# PGS_4.net
KiCad netlist of a schematic drawn in Altium Designer
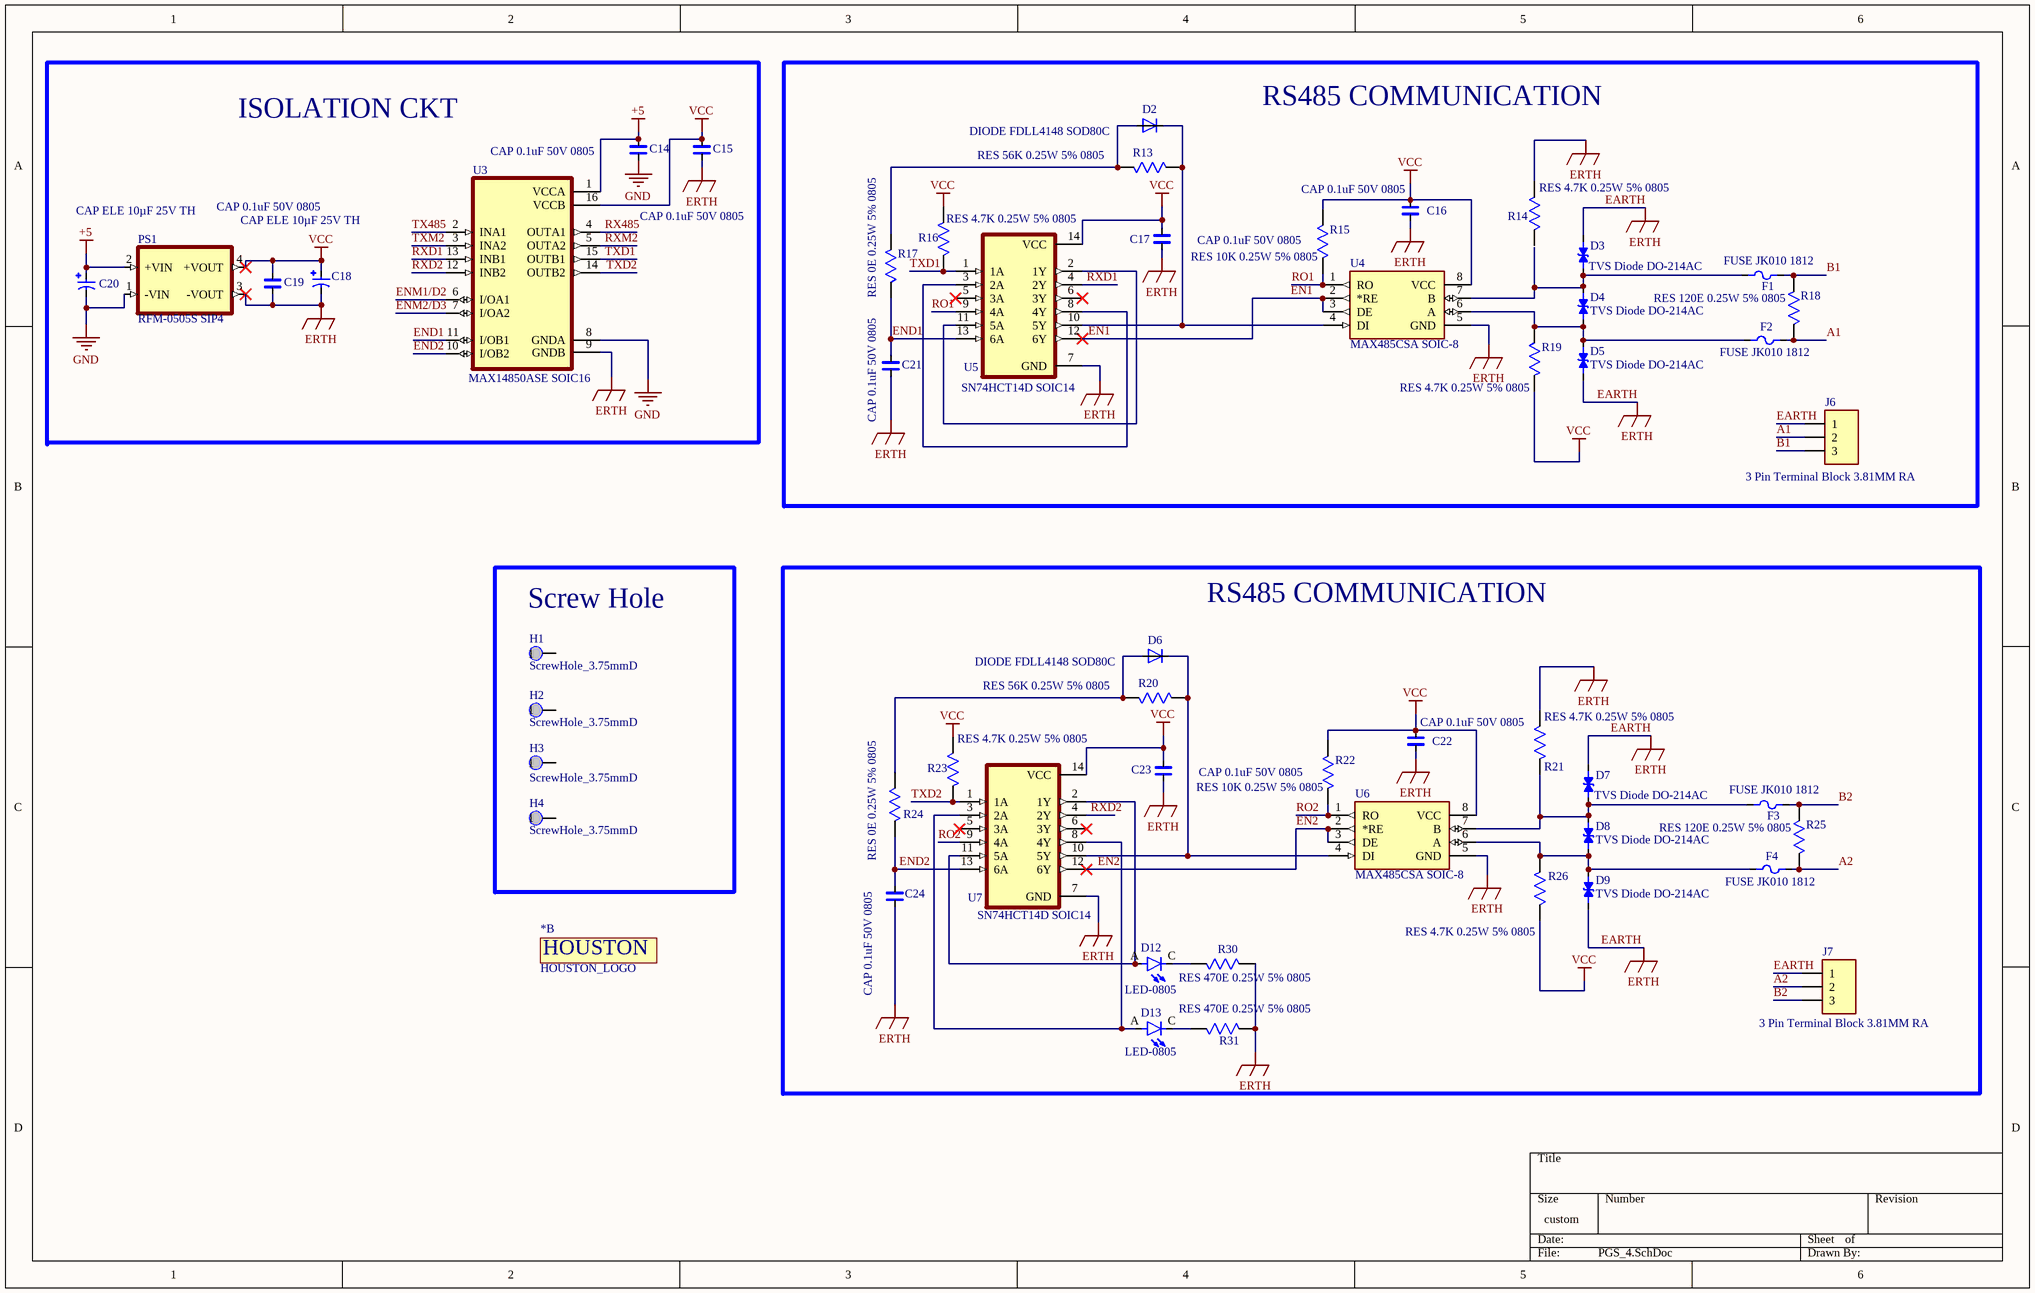
[diagram p0: PGS_4.SchDoc]

(export (version "E")
  (design (tool "Eeschema 10.0.6"))
  (components
    (comp (ref "*")
      (value "HOUSTON_LOGO")
      (footprint "HOUSTON_LOGO")
      (libsource (lib "PGS") (part "HOUSTON_LOGO"))
    )
    (comp (ref "C14")
      (value "CAP 0.1uF 50V 0805")
      (footprint "CAP CER 0.1uF/50V 5%")
      (description "CAP CER 0.1uF/50V  Ceramic Capacitor X7R 0805 (2012 Metric)")
      (fields (field (name "MF") "Samsung") (field (name "MP") "CL21B104KCFNNNE"))
      (libsource (lib "PGS") (part "CAP CER 0.1uF/50V 5%"))
    )
    (comp (ref "C15")
      (value "CAP 0.1uF 50V 0805")
      (footprint "CAP CER 0.1uF/50V 5%")
      (description "CAP CER 0.1uF/50V  Ceramic Capacitor X7R 0805 (2012 Metric)")
      (fields (field (name "MF") "Samsung") (field (name "MP") "CL21B104KCFNNNE"))
      (libsource (lib "PGS") (part "CAP CER 0.1uF/50V 5%"))
    )
    (comp (ref "C16")
      (value "CAP 0.1uF 50V 0805")
      (footprint "CAP CER 0.1uF/50V 5%")
      (description "CAP CER 0.1uF/50V  Ceramic Capacitor X7R 0805 (2012 Metric)")
      (fields (field (name "MF") "Samsung") (field (name "MP") "CL21B104KCFNNNE"))
      (libsource (lib "PGS") (part "CAP CER 0.1uF/50V 5%"))
    )
    (comp (ref "C17")
      (value "CAP 0.1uF 50V 0805")
      (footprint "CAP CER 0.1uF/50V 5%")
      (description "CAP CER 0.1uF/50V  Ceramic Capacitor X7R 0805 (2012 Metric)")
      (fields (field (name "MF") "Samsung") (field (name "MP") "CL21B104KCFNNNE"))
      (libsource (lib "PGS") (part "CAP CER 0.1uF/50V 5%"))
    )
    (comp (ref "C18")
      (value "CAP ELE 10µF 25V TH")
      (footprint "CAP ELE 10µF 25V TH")
      (description "10µF 25V Aluminum Electrolytic Capacitors Radial Lead Type TH, Dia-5mm, Pitch-2mm ECEA1EN100UI")
      (fields (field (name "MF") "Panasonic") (field (name "DIGI-KEY_PART_NUMBER") "ECE-A1EN100UI-ND"))
      (libsource (lib "PGS") (part "CAP ELE 10µF 25V TH"))
    )
    (comp (ref "C19")
      (value "CAP 0.1uF 50V 0805")
      (footprint "CAP CER 0.1uF/50V 5%")
      (description "CAP CER 0.1uF/50V  Ceramic Capacitor X7R 0805 (2012 Metric)")
      (fields (field (name "MF") "Samsung") (field (name "MP") "CL21B104KCFNNNE"))
      (libsource (lib "PGS") (part "CAP CER 0.1uF/50V 5%"))
    )
    (comp (ref "C20")
      (value "CAP ELE 10µF 25V TH")
      (footprint "CAP ELE 10µF 25V TH")
      (description "10µF 25V Aluminum Electrolytic Capacitors Radial Lead Type TH, Dia-5mm, Pitch-2mm ECEA1EN100UI")
      (fields (field (name "MF") "Panasonic") (field (name "DIGI-KEY_PART_NUMBER") "ECE-A1EN100UI-ND"))
      (libsource (lib "PGS") (part "CAP ELE 10µF 25V TH"))
    )
    (comp (ref "C21")
      (value "CAP 0.1uF 50V 0805")
      (footprint "CAP CER 0.1uF/50V 5%")
      (description "CAP CER 0.1uF/50V  Ceramic Capacitor X7R 0805 (2012 Metric)")
      (fields (field (name "MF") "Samsung") (field (name "MP") "CL21B104KCFNNNE"))
      (libsource (lib "PGS") (part "CAP CER 0.1uF/50V 5%"))
    )
    (comp (ref "C22")
      (value "CAP 0.1uF 50V 0805")
      (footprint "CAP CER 0.1uF/50V 5%")
      (description "CAP CER 0.1uF/50V  Ceramic Capacitor X7R 0805 (2012 Metric)")
      (fields (field (name "MF") "Samsung") (field (name "MP") "CL21B104KCFNNNE"))
      (libsource (lib "PGS") (part "CAP CER 0.1uF/50V 5%"))
    )
    (comp (ref "C23")
      (value "CAP 0.1uF 50V 0805")
      (footprint "CAP CER 0.1uF/50V 5%")
      (description "CAP CER 0.1uF/50V  Ceramic Capacitor X7R 0805 (2012 Metric)")
      (fields (field (name "MF") "Samsung") (field (name "MP") "CL21B104KCFNNNE"))
      (libsource (lib "PGS") (part "CAP CER 0.1uF/50V 5%"))
    )
    (comp (ref "C24")
      (value "CAP 0.1uF 50V 0805")
      (footprint "CAP CER 0.1uF/50V 5%")
      (description "CAP CER 0.1uF/50V  Ceramic Capacitor X7R 0805 (2012 Metric)")
      (fields (field (name "MF") "Samsung") (field (name "MP") "CL21B104KCFNNNE"))
      (libsource (lib "PGS") (part "CAP CER 0.1uF/50V 5%"))
    )
    (comp (ref "D2")
      (value "DIODE FDLL4148 SOD80C")
      (footprint "DIODE SOD80C")
      (description "FDLL4148 Diode Standard 75V 200mA _DC_ Surface Mount LLDS; MiniMelf DIODE SOD80C PMLL4148L")
      (fields (field (name "MF") "Nexperia USA") (field (name "MP") "PMLL4148L"))
      (libsource (lib "PGS") (part "DIODE FDLL4148 SOD80C"))
    )
    (comp (ref "D3")
      (value "TVS Diode DO-214AC")
      (footprint "TVS Diode DO-214AC")
      (description "TVS Diode BiDirectional LittileFuse 1.5SMC6.8CA DO-214AC 6V8C")
      (fields (field (name "MP") "SMAJ7.5CA"))
      (libsource (lib "PGS") (part "TVS Diode DO-214AC"))
    )
    (comp (ref "D4")
      (value "TVS Diode DO-214AC")
      (footprint "TVS Diode DO-214AC")
      (description "TVS Diode BiDirectional LittileFuse 1.5SMC6.8CA DO-214AC 6V8C")
      (fields (field (name "MP") "SMAJ7.5CA"))
      (libsource (lib "PGS") (part "TVS Diode DO-214AC"))
    )
    (comp (ref "D5")
      (value "TVS Diode DO-214AC")
      (footprint "TVS Diode DO-214AC")
      (description "TVS Diode BiDirectional LittileFuse 1.5SMC6.8CA DO-214AC 6V8C")
      (fields (field (name "MP") "SMAJ7.5CA"))
      (libsource (lib "PGS") (part "TVS Diode DO-214AC"))
    )
    (comp (ref "D6")
      (value "DIODE FDLL4148 SOD80C")
      (footprint "DIODE SOD80C")
      (description "FDLL4148 Diode Standard 75V 200mA _DC_ Surface Mount LLDS; MiniMelf DIODE SOD80C PMLL4148L")
      (fields (field (name "MF") "Nexperia USA") (field (name "MP") "PMLL4148L"))
      (libsource (lib "PGS") (part "DIODE FDLL4148 SOD80C"))
    )
    (comp (ref "D7")
      (value "TVS Diode DO-214AC")
      (footprint "TVS Diode DO-214AC")
      (description "TVS Diode BiDirectional LittileFuse 1.5SMC6.8CA DO-214AC 6V8C")
      (fields (field (name "MP") "SMAJ7.5CA"))
      (libsource (lib "PGS") (part "TVS Diode DO-214AC"))
    )
    (comp (ref "D8")
      (value "TVS Diode DO-214AC")
      (footprint "TVS Diode DO-214AC")
      (description "TVS Diode BiDirectional LittileFuse 1.5SMC6.8CA DO-214AC 6V8C")
      (fields (field (name "MP") "SMAJ7.5CA"))
      (libsource (lib "PGS") (part "TVS Diode DO-214AC"))
    )
    (comp (ref "D9")
      (value "TVS Diode DO-214AC")
      (footprint "TVS Diode DO-214AC")
      (description "TVS Diode BiDirectional LittileFuse 1.5SMC6.8CA DO-214AC 6V8C")
      (fields (field (name "MP") "SMAJ7.5CA"))
      (libsource (lib "PGS") (part "TVS Diode DO-214AC"))
    )
    (comp (ref "D12")
      (value "LED-0805")
      (footprint "LED-0805")
      (description "Red 640nm LED Indication - Discrete 1.85V 0805 (2012 Metric) SMT APT2012SRCPRV")
      (fields (field (name "MF") "Kingbright") (field (name "MP") "APT2012SRCPRV"))
      (libsource (lib "PGS") (part "LED-0805"))
    )
    (comp (ref "D13")
      (value "LED-0805")
      (footprint "LED-0805")
      (description "Red 640nm LED Indication - Discrete 1.85V 0805 (2012 Metric) SMT APT2012SRCPRV")
      (fields (field (name "MF") "Kingbright") (field (name "MP") "APT2012SRCPRV"))
      (libsource (lib "PGS") (part "LED-0805"))
    )
    (comp (ref "F1")
      (value "FUSE JK010 1812")
      (footprint "FUSE JK010 1812")
      (fields (field (name "MP") "MF-MSMF010-2") (field (name "MF") "Bourns"))
      (libsource (lib "PGS") (part "FUSE JK010 1812"))
    )
    (comp (ref "F2")
      (value "FUSE JK010 1812")
      (footprint "FUSE JK010 1812")
      (fields (field (name "MP") "MF-MSMF010-2") (field (name "MF") "Bourns"))
      (libsource (lib "PGS") (part "FUSE JK010 1812"))
    )
    (comp (ref "F3")
      (value "FUSE JK010 1812")
      (footprint "FUSE JK010 1812")
      (fields (field (name "MP") "MF-MSMF010-2") (field (name "MF") "Bourns"))
      (libsource (lib "PGS") (part "FUSE JK010 1812"))
    )
    (comp (ref "F4")
      (value "FUSE JK010 1812")
      (footprint "FUSE JK010 1812")
      (fields (field (name "MP") "MF-MSMF010-2") (field (name "MF") "Bourns"))
      (libsource (lib "PGS") (part "FUSE JK010 1812"))
    )
    (comp (ref "H1")
      (value "ScrewHole_3.75mmD")
      (footprint "ScrewHole_3.75mmD - duplicate")
      (description "SCREW HEAD DIA 4.5MM, SREW LEG DIA 3 MM")
      (libsource (lib "PGS") (part "ScrewHole_3.75mmD"))
    )
    (comp (ref "H2")
      (value "ScrewHole_3.75mmD")
      (footprint "ScrewHole_3.75mmD - duplicate")
      (description "SCREW HEAD DIA 4.5MM, SREW LEG DIA 3 MM")
      (libsource (lib "PGS") (part "ScrewHole_3.75mmD"))
    )
    (comp (ref "H3")
      (value "ScrewHole_3.75mmD")
      (footprint "ScrewHole_3.75mmD - duplicate")
      (description "SCREW HEAD DIA 4.5MM, SREW LEG DIA 3 MM")
      (libsource (lib "PGS") (part "ScrewHole_3.75mmD"))
    )
    (comp (ref "H4")
      (value "ScrewHole_3.75mmD")
      (footprint "ScrewHole_3.75mmD - duplicate")
      (description "SCREW HEAD DIA 4.5MM, SREW LEG DIA 3 MM")
      (libsource (lib "PGS") (part "ScrewHole_3.75mmD"))
    )
    (comp (ref "J6")
      (value "3 Pin Terminal Block 3.81MM RA")
      (footprint "3 Pin Terminal Block 3.81MM RA")
      (description "3 Pin Terminal Block HDR 3.81MM THT RA 284513-3")
      (fields (field (name "MP") "284513-3") (field (name "MF") "TE Connectivity"))
      (libsource (lib "PGS") (part "3 Pin Terminal Block 3.81MM RA"))
    )
    (comp (ref "J7")
      (value "3 Pin Terminal Block 3.81MM RA")
      (footprint "3 Pin Terminal Block 3.81MM RA")
      (description "3 Pin Terminal Block HDR 3.81MM THT RA 284513-3")
      (fields (field (name "MP") "284513-3") (field (name "MF") "TE Connectivity"))
      (libsource (lib "PGS") (part "3 Pin Terminal Block 3.81MM RA"))
    )
    (comp (ref "PS1")
      (value "RFM-0505S SIP4")
      (footprint "RFM-0505S")
      (fields (field (name "MF") "Recom Power") (field (name "MP") "RFM-0505S"))
      (libsource (lib "PGS") (part "RFM-0505S"))
    )
    (comp (ref "R13")
      (value "RES 56K 0.25W 5% 0805")
      (footprint "RES 0805 10K/0.25W 5%")
      (description "RESISTOR, THICK FILM, 10K, 5%, 0805 0.25W")
      (fields (field (name "MP") "ERJ-6GEYJ103V") (field (name "MF") "Panasonic Electronic"))
      (libsource (lib "PGS") (part "RES 10K 0.25W 5% 0805"))
    )
    (comp (ref "R14")
      (value "RES 4.7K 0.25W 5% 0805")
      (footprint "RES 0805 10K/0.25W 5%")
      (description "RESISTOR, THICK FILM, 10K, 5%, 0805 0.25W")
      (fields (field (name "MP") "ERJ-6GEYJ103V") (field (name "MF") "Panasonic Electronic"))
      (libsource (lib "PGS") (part "RES 10K 0.25W 5% 0805"))
    )
    (comp (ref "R15")
      (value "RES 10K 0.25W 5% 0805")
      (footprint "RES 0805 10K/0.25W 5%")
      (description "RESISTOR, THICK FILM, 10K, 5%, 0805 0.25W")
      (fields (field (name "MP") "ERJ-6GEYJ103V") (field (name "MF") "Panasonic Electronic"))
      (libsource (lib "PGS") (part "RES 10K 0.25W 5% 0805"))
    )
    (comp (ref "R16")
      (value "RES 4.7K 0.25W 5% 0805")
      (footprint "RES 0805 10K/0.25W 5%")
      (description "RESISTOR, THICK FILM, 10K, 5%, 0805 0.25W")
      (fields (field (name "MP") "ERJ-6GEYJ103V") (field (name "MF") "Panasonic Electronic"))
      (libsource (lib "PGS") (part "RES 10K 0.25W 5% 0805"))
    )
    (comp (ref "R17")
      (value "RES 0E 0.25W 5% 0805")
      (footprint "RES 0805 10K/0.25W 5%")
      (description "RESISTOR, THICK FILM, 10K, 5%, 0805 0.25W")
      (fields (field (name "MP") "ERJ-6GEYJ103V") (field (name "MF") "Panasonic Electronic"))
      (libsource (lib "PGS") (part "RES 10K 0.25W 5% 0805"))
    )
    (comp (ref "R18")
      (value "RES 120E 0.25W 5% 0805")
      (footprint "RES 0805 10K/0.25W 5%")
      (description "RESISTOR, THICK FILM, 10K, 5%, 0805 0.25W")
      (fields (field (name "MP") "ERJ-6GEYJ103V") (field (name "MF") "Panasonic Electronic"))
      (libsource (lib "PGS") (part "RES 10K 0.25W 5% 0805"))
    )
    (comp (ref "R19")
      (value "RES 4.7K 0.25W 5% 0805")
      (footprint "RES 0805 10K/0.25W 5%")
      (description "RESISTOR, THICK FILM, 10K, 5%, 0805 0.25W")
      (fields (field (name "MP") "ERJ-6GEYJ103V") (field (name "MF") "Panasonic Electronic"))
      (libsource (lib "PGS") (part "RES 10K 0.25W 5% 0805"))
    )
    (comp (ref "R20")
      (value "RES 56K 0.25W 5% 0805")
      (footprint "RES 0805 10K/0.25W 5%")
      (description "RESISTOR, THICK FILM, 10K, 5%, 0805 0.25W")
      (fields (field (name "MP") "ERJ-6GEYJ103V") (field (name "MF") "Panasonic Electronic"))
      (libsource (lib "PGS") (part "RES 10K 0.25W 5% 0805"))
    )
    (comp (ref "R21")
      (value "RES 4.7K 0.25W 5% 0805")
      (footprint "RES 0805 10K/0.25W 5%")
      (description "RESISTOR, THICK FILM, 10K, 5%, 0805 0.25W")
      (fields (field (name "MP") "ERJ-6GEYJ103V") (field (name "MF") "Panasonic Electronic"))
      (libsource (lib "PGS") (part "RES 10K 0.25W 5% 0805"))
    )
    (comp (ref "R22")
      (value "RES 10K 0.25W 5% 0805")
      (footprint "RES 0805 10K/0.25W 5%")
      (description "RESISTOR, THICK FILM, 10K, 5%, 0805 0.25W")
      (fields (field (name "MP") "ERJ-6GEYJ103V") (field (name "MF") "Panasonic Electronic"))
      (libsource (lib "PGS") (part "RES 10K 0.25W 5% 0805"))
    )
    (comp (ref "R23")
      (value "RES 4.7K 0.25W 5% 0805")
      (footprint "RES 0805 10K/0.25W 5%")
      (description "RESISTOR, THICK FILM, 10K, 5%, 0805 0.25W")
      (fields (field (name "MP") "ERJ-6GEYJ103V") (field (name "MF") "Panasonic Electronic"))
      (libsource (lib "PGS") (part "RES 10K 0.25W 5% 0805"))
    )
    (comp (ref "R24")
      (value "RES 0E 0.25W 5% 0805")
      (footprint "RES 0805 10K/0.25W 5%")
      (description "RESISTOR, THICK FILM, 10K, 5%, 0805 0.25W")
      (fields (field (name "MP") "ERJ-6GEYJ103V") (field (name "MF") "Panasonic Electronic"))
      (libsource (lib "PGS") (part "RES 10K 0.25W 5% 0805"))
    )
    (comp (ref "R25")
      (value "RES 120E 0.25W 5% 0805")
      (footprint "RES 0805 10K/0.25W 5%")
      (description "RESISTOR, THICK FILM, 10K, 5%, 0805 0.25W")
      (fields (field (name "MP") "ERJ-6GEYJ103V") (field (name "MF") "Panasonic Electronic"))
      (libsource (lib "PGS") (part "RES 10K 0.25W 5% 0805"))
    )
    (comp (ref "R26")
      (value "RES 4.7K 0.25W 5% 0805")
      (footprint "RES 0805 10K/0.25W 5%")
      (description "RESISTOR, THICK FILM, 10K, 5%, 0805 0.25W")
      (fields (field (name "MP") "ERJ-6GEYJ103V") (field (name "MF") "Panasonic Electronic"))
      (libsource (lib "PGS") (part "RES 10K 0.25W 5% 0805"))
    )
    (comp (ref "R30")
      (value "RES 470E 0.25W 5% 0805")
      (footprint "RES 0805 10K/0.25W 5%")
      (description "RESISTOR, THICK FILM, 10K, 5%, 0805 0.25W SMT")
      (fields (field (name "MP") "ERJ-6GEYJ103V") (field (name "MF") "Panasonic Electronic"))
      (libsource (lib "PGS") (part "RES 10K 0.25W 5% 0805"))
    )
    (comp (ref "R31")
      (value "RES 470E 0.25W 5% 0805")
      (footprint "RES 0805 10K/0.25W 5%")
      (description "RESISTOR, THICK FILM, 10K, 5%, 0805 0.25W SMT")
      (fields (field (name "MP") "ERJ-6GEYJ103V") (field (name "MF") "Panasonic Electronic"))
      (libsource (lib "PGS") (part "RES 10K 0.25W 5% 0805"))
    )
    (comp (ref "U3")
      (value "MAX14850ASE SOIC16")
      (footprint "MAX14850ASE")
      (description "MAX14850ASE SOIC16 Six-Channel Digital Isolator")
      (fields (field (name "MF") "Analog Devices") (field (name "MP") "MAX14850ASE+T"))
      (libsource (lib "PGS") (part "MAX14850ASE+T"))
    )
    (comp (ref "U4")
      (value "MAX485CSA SOIC-8")
      (footprint "MAX485CSA")
      (description "MAX485CSA-RS-485/RS-422 Transceivers, SOIC-8")
      (fields (field (name "MF") "Analog Devices") (field (name "MP") "MAX485CSA+"))
      (libsource (lib "PGS") (part "MAX485CSA"))
    )
    (comp (ref "U5")
      (value "SN74HCT14D SOIC14")
      (footprint "SN74HCT14D SOIC14")
      (description "SN74HCT14D SOIC14 6-ch, 4.5-V to 5.5-V inverters with Schmitt-Trigger inputs")
      (fields (field (name "MF") "Texas Instruments") (field (name "MP") "SN74HCT14D"))
      (libsource (lib "PGS") (part "SN74HCT14D"))
    )
    (comp (ref "U6")
      (value "MAX485CSA SOIC-8")
      (footprint "MAX485CSA")
      (description "MAX485CSA-RS-485/RS-422 Transceivers, SOIC-8")
      (fields (field (name "MF") "Analog Devices") (field (name "MP") "MAX485CSA+"))
      (libsource (lib "PGS") (part "MAX485CSA"))
    )
    (comp (ref "U7")
      (value "SN74HCT14D SOIC14")
      (footprint "SN74HCT14D SOIC14")
      (description "SN74HCT14D SOIC14 6-ch, 4.5-V to 5.5-V inverters with Schmitt-Trigger inputs")
      (fields (field (name "MF") "Texas Instruments") (field (name "MP") "SN74HCT14D"))
      (libsource (lib "PGS") (part "SN74HCT14D"))
    )
  )
  (nets
    (net (code "1") (name "+5") (class "Default")
      (node (ref "C14") (pin "2") (pinfunction "2_2") (pintype "passive"))
      (node (ref "C20") (pin "P") (pinfunction "P_P") (pintype "passive"))
      (node (ref "PS1") (pin "2") (pinfunction "+VIN_2") (pintype "input"))
      (node (ref "U3") (pin "1") (pinfunction "VCCA_1") (pintype "power_in"))
    )
    (net (code "2") (name "/A1") (class "Default")
      (node (ref "F2") (pin "2") (pinfunction "2_2") (pintype "passive"))
      (node (ref "J6") (pin "2") (pinfunction "2_2") (pintype "passive"))
      (node (ref "R18") (pin "1") (pinfunction "1_1") (pintype "passive"))
    )
    (net (code "3") (name "/A2") (class "Default")
      (node (ref "F4") (pin "2") (pinfunction "2_2") (pintype "passive"))
      (node (ref "J7") (pin "2") (pinfunction "2_2") (pintype "passive"))
      (node (ref "R25") (pin "1") (pinfunction "1_1") (pintype "passive"))
    )
    (net (code "4") (name "/B1") (class "Default")
      (node (ref "F1") (pin "2") (pinfunction "2_2") (pintype "passive"))
      (node (ref "J6") (pin "3") (pinfunction "3_3") (pintype "passive"))
      (node (ref "R18") (pin "2") (pinfunction "2_2") (pintype "passive"))
    )
    (net (code "5") (name "/B2") (class "Default")
      (node (ref "F3") (pin "2") (pinfunction "2_2") (pintype "passive"))
      (node (ref "J7") (pin "3") (pinfunction "3_3") (pintype "passive"))
      (node (ref "R25") (pin "2") (pinfunction "2_2") (pintype "passive"))
    )
    (net (code "6") (name "/EN1") (class "Default")
      (node (ref "U4") (pin "2") (pinfunction "*RE_2") (pintype "output"))
      (node (ref "U4") (pin "3") (pinfunction "DE_3") (pintype "output"))
      (node (ref "U5") (pin "12") (pinfunction "6Y_12") (pintype "output"))
    )
    (net (code "7") (name "/EN2") (class "Default")
      (node (ref "U6") (pin "2") (pinfunction "*RE_2") (pintype "output"))
      (node (ref "U6") (pin "3") (pinfunction "DE_3") (pintype "output"))
      (node (ref "U7") (pin "12") (pinfunction "6Y_12") (pintype "output"))
    )
    (net (code "8") (name "/END1") (class "Default")
      (node (ref "C21") (pin "2") (pinfunction "2_2") (pintype "passive"))
      (node (ref "R17") (pin "1") (pinfunction "1_1") (pintype "passive"))
      (node (ref "U3") (pin "11") (pinfunction "I/OB1_11") (pintype "bidirectional"))
      (node (ref "U5") (pin "13") (pinfunction "6A_13") (pintype "input"))
    )
    (net (code "9") (name "/END2") (class "Default")
      (node (ref "C24") (pin "2") (pinfunction "2_2") (pintype "passive"))
      (node (ref "R24") (pin "1") (pinfunction "1_1") (pintype "passive"))
      (node (ref "U3") (pin "10") (pinfunction "I/OB2_10") (pintype "bidirectional"))
      (node (ref "U7") (pin "13") (pinfunction "6A_13") (pintype "input"))
    )
    (net (code "10") (name "/ENM1{slash}D2") (class "Default")
      (node (ref "U3") (pin "6") (pinfunction "I/OA1_6") (pintype "bidirectional"))
    )
    (net (code "11") (name "/ENM2{slash}D3") (class "Default")
      (node (ref "U3") (pin "7") (pinfunction "I/OA2_7") (pintype "bidirectional"))
    )
    (net (code "12") (name "/RO1") (class "Default")
      (node (ref "R15") (pin "1") (pinfunction "1_1") (pintype "passive"))
      (node (ref "U4") (pin "1") (pinfunction "RO_1") (pintype "output"))
      (node (ref "U5") (pin "9") (pinfunction "4A_9") (pintype "input"))
    )
    (net (code "13") (name "/RO2") (class "Default")
      (node (ref "R22") (pin "1") (pinfunction "1_1") (pintype "passive"))
      (node (ref "U6") (pin "1") (pinfunction "RO_1") (pintype "output"))
      (node (ref "U7") (pin "9") (pinfunction "4A_9") (pintype "input"))
    )
    (net (code "14") (name "/RX485") (class "Default")
      (node (ref "U3") (pin "4") (pinfunction "OUTA1_4") (pintype "output"))
    )
    (net (code "15") (name "/RXD1") (class "Default")
      (node (ref "U3") (pin "13") (pinfunction "INB1_13") (pintype "input"))
      (node (ref "U5") (pin "4") (pinfunction "2Y_4") (pintype "output"))
    )
    (net (code "16") (name "/RXD2") (class "Default")
      (node (ref "U3") (pin "12") (pinfunction "INB2_12") (pintype "input"))
      (node (ref "U7") (pin "4") (pinfunction "2Y_4") (pintype "output"))
    )
    (net (code "17") (name "/RXM2") (class "Default")
      (node (ref "U3") (pin "5") (pinfunction "OUTA2_5") (pintype "output"))
    )
    (net (code "18") (name "/TX485") (class "Default")
      (node (ref "U3") (pin "2") (pinfunction "INA1_2") (pintype "input"))
    )
    (net (code "19") (name "/TXD1") (class "Default")
      (node (ref "R16") (pin "1") (pinfunction "1_1") (pintype "passive"))
      (node (ref "U3") (pin "15") (pinfunction "OUTB1_15") (pintype "output"))
      (node (ref "U5") (pin "1") (pinfunction "1A_1") (pintype "input"))
    )
    (net (code "20") (name "/TXD2") (class "Default")
      (node (ref "R23") (pin "1") (pinfunction "1_1") (pintype "passive"))
      (node (ref "U3") (pin "14") (pinfunction "OUTB2_14") (pintype "output"))
      (node (ref "U7") (pin "1") (pinfunction "1A_1") (pintype "input"))
    )
    (net (code "21") (name "/TXM2") (class "Default")
      (node (ref "U3") (pin "3") (pinfunction "INA2_3") (pintype "input"))
    )
    (net (code "22") (name "ERTH") (class "Default")
      (node (ref "C15") (pin "1") (pinfunction "1_1") (pintype "passive"))
      (node (ref "C16") (pin "1") (pinfunction "1_1") (pintype "passive"))
      (node (ref "C17") (pin "1") (pinfunction "1_1") (pintype "passive"))
      (node (ref "C18") (pin "N") (pinfunction "N_N") (pintype "passive"))
      (node (ref "C19") (pin "1") (pinfunction "1_1") (pintype "passive"))
      (node (ref "C21") (pin "1") (pinfunction "1_1") (pintype "passive"))
      (node (ref "C22") (pin "1") (pinfunction "1_1") (pintype "passive"))
      (node (ref "C23") (pin "1") (pinfunction "1_1") (pintype "passive"))
      (node (ref "C24") (pin "1") (pinfunction "1_1") (pintype "passive"))
      (node (ref "D3") (pin "2") (pinfunction "2_2") (pintype "passive"))
      (node (ref "D5") (pin "1") (pinfunction "1_1") (pintype "passive"))
      (node (ref "D7") (pin "2") (pinfunction "2_2") (pintype "passive"))
      (node (ref "D9") (pin "1") (pinfunction "1_1") (pintype "passive"))
      (node (ref "J6") (pin "1") (pinfunction "1_1") (pintype "passive"))
      (node (ref "J7") (pin "1") (pinfunction "1_1") (pintype "passive"))
      (node (ref "PS1") (pin "3") (pinfunction "-VOUT_3") (pintype "output"))
      (node (ref "R14") (pin "2") (pinfunction "2_2") (pintype "passive"))
      (node (ref "R21") (pin "2") (pinfunction "2_2") (pintype "passive"))
      (node (ref "R30") (pin "2") (pinfunction "2_2") (pintype "passive"))
      (node (ref "R31") (pin "2") (pinfunction "2_2") (pintype "passive"))
      (node (ref "U3") (pin "9") (pinfunction "GNDB_9") (pintype "power_in"))
      (node (ref "U4") (pin "5") (pinfunction "GND_5") (pintype "power_in"))
      (node (ref "U5") (pin "7") (pinfunction "GND_7") (pintype "power_in"))
      (node (ref "U6") (pin "5") (pinfunction "GND_5") (pintype "power_in"))
      (node (ref "U7") (pin "7") (pinfunction "GND_7") (pintype "power_in"))
    )
    (net (code "23") (name "GND") (class "Default")
      (node (ref "C14") (pin "1") (pinfunction "1_1") (pintype "passive"))
      (node (ref "C20") (pin "N") (pinfunction "N_N") (pintype "passive"))
      (node (ref "PS1") (pin "1") (pinfunction "-VIN_1") (pintype "input"))
      (node (ref "U3") (pin "8") (pinfunction "GNDA_8") (pintype "power_in"))
    )
    (net (code "24") (name "Net-(D2-A)") (class "Default")
      (node (ref "D2") (pin "2") (pinfunction "A_2") (pintype "passive"))
      (node (ref "R13") (pin "2") (pinfunction "2_2") (pintype "passive"))
      (node (ref "R17") (pin "2") (pinfunction "2_2") (pintype "passive"))
    )
    (net (code "25") (name "Net-(D2-K)") (class "Default")
      (node (ref "D2") (pin "1") (pinfunction "K_1") (pintype "passive"))
      (node (ref "R13") (pin "1") (pinfunction "1_1") (pintype "passive"))
      (node (ref "U4") (pin "4") (pinfunction "DI_4") (pintype "input"))
      (node (ref "U5") (pin "10") (pinfunction "5Y_10") (pintype "output"))
    )
    (net (code "26") (name "Net-(D6-A)") (class "Default")
      (node (ref "D6") (pin "2") (pinfunction "A_2") (pintype "passive"))
      (node (ref "R20") (pin "2") (pinfunction "2_2") (pintype "passive"))
      (node (ref "R24") (pin "2") (pinfunction "2_2") (pintype "passive"))
    )
    (net (code "27") (name "Net-(D6-K)") (class "Default")
      (node (ref "D6") (pin "1") (pinfunction "K_1") (pintype "passive"))
      (node (ref "R20") (pin "1") (pinfunction "1_1") (pintype "passive"))
      (node (ref "U6") (pin "4") (pinfunction "DI_4") (pintype "input"))
      (node (ref "U7") (pin "10") (pinfunction "5Y_10") (pintype "output"))
    )
    (net (code "28") (name "Net-(D12-PadC)") (class "Default")
      (node (ref "D12") (pin "C") (pinfunction "C_C") (pintype "passive"))
      (node (ref "R30") (pin "1") (pinfunction "1_1") (pintype "passive"))
    )
    (net (code "29") (name "Net-(D13-PadC)") (class "Default")
      (node (ref "D13") (pin "C") (pinfunction "C_C") (pintype "passive"))
      (node (ref "R31") (pin "1") (pinfunction "1_1") (pintype "passive"))
    )
    (net (code "30") (name "Net-(U4-A)") (class "Default")
      (node (ref "D4") (pin "1") (pinfunction "1_1") (pintype "passive"))
      (node (ref "D5") (pin "2") (pinfunction "2_2") (pintype "passive"))
      (node (ref "F2") (pin "1") (pinfunction "1_1") (pintype "passive"))
      (node (ref "R19") (pin "2") (pinfunction "2_2") (pintype "passive"))
      (node (ref "U4") (pin "6") (pinfunction "A_6") (pintype "bidirectional"))
    )
    (net (code "31") (name "Net-(U4-B)") (class "Default")
      (node (ref "D3") (pin "1") (pinfunction "1_1") (pintype "passive"))
      (node (ref "D4") (pin "2") (pinfunction "2_2") (pintype "passive"))
      (node (ref "F1") (pin "1") (pinfunction "1_1") (pintype "passive"))
      (node (ref "U4") (pin "7") (pinfunction "B_7") (pintype "bidirectional"))
    )
    (net (code "32") (name "Net-(U5-1Y)") (class "Default")
      (node (ref "U5") (pin "11") (pinfunction "5A_11") (pintype "input"))
      (node (ref "U5") (pin "2") (pinfunction "1Y_2") (pintype "output"))
    )
    (net (code "33") (name "Net-(U5-2A)") (class "Default")
      (node (ref "U5") (pin "3") (pinfunction "2A_3") (pintype "input"))
      (node (ref "U5") (pin "8") (pinfunction "4Y_8") (pintype "output"))
    )
    (net (code "34") (name "Net-(U6-A)") (class "Default")
      (node (ref "D8") (pin "1") (pinfunction "1_1") (pintype "passive"))
      (node (ref "D9") (pin "2") (pinfunction "2_2") (pintype "passive"))
      (node (ref "F4") (pin "1") (pinfunction "1_1") (pintype "passive"))
      (node (ref "R26") (pin "2") (pinfunction "2_2") (pintype "passive"))
      (node (ref "U6") (pin "6") (pinfunction "A_6") (pintype "bidirectional"))
    )
    (net (code "35") (name "Net-(U6-B)") (class "Default")
      (node (ref "D7") (pin "1") (pinfunction "1_1") (pintype "passive"))
      (node (ref "D8") (pin "2") (pinfunction "2_2") (pintype "passive"))
      (node (ref "F3") (pin "1") (pinfunction "1_1") (pintype "passive"))
      (node (ref "R21") (pin "1") (pinfunction "1_1") (pintype "passive"))
      (node (ref "U6") (pin "7") (pinfunction "B_7") (pintype "bidirectional"))
    )
    (net (code "36") (name "Net-(U7-1Y)") (class "Default")
      (node (ref "D12") (pin "A") (pinfunction "A_A") (pintype "passive"))
      (node (ref "U7") (pin "11") (pinfunction "5A_11") (pintype "input"))
      (node (ref "U7") (pin "2") (pinfunction "1Y_2") (pintype "output"))
    )
    (net (code "37") (name "Net-(U7-2A)") (class "Default")
      (node (ref "D13") (pin "A") (pinfunction "A_A") (pintype "passive"))
      (node (ref "U7") (pin "3") (pinfunction "2A_3") (pintype "input"))
      (node (ref "U7") (pin "8") (pinfunction "4Y_8") (pintype "output"))
    )
    (net (code "38") (name "VCC") (class "Default")
      (node (ref "C15") (pin "2") (pinfunction "2_2") (pintype "passive"))
      (node (ref "C16") (pin "2") (pinfunction "2_2") (pintype "passive"))
      (node (ref "C17") (pin "2") (pinfunction "2_2") (pintype "passive"))
      (node (ref "C18") (pin "P") (pinfunction "P_P") (pintype "passive"))
      (node (ref "C19") (pin "2") (pinfunction "2_2") (pintype "passive"))
      (node (ref "C22") (pin "2") (pinfunction "2_2") (pintype "passive"))
      (node (ref "C23") (pin "2") (pinfunction "2_2") (pintype "passive"))
      (node (ref "PS1") (pin "4") (pinfunction "+VOUT_4") (pintype "output"))
      (node (ref "R15") (pin "2") (pinfunction "2_2") (pintype "passive"))
      (node (ref "R16") (pin "2") (pinfunction "2_2") (pintype "passive"))
      (node (ref "R19") (pin "1") (pinfunction "1_1") (pintype "passive"))
      (node (ref "R22") (pin "2") (pinfunction "2_2") (pintype "passive"))
      (node (ref "R23") (pin "2") (pinfunction "2_2") (pintype "passive"))
      (node (ref "R26") (pin "1") (pinfunction "1_1") (pintype "passive"))
      (node (ref "U3") (pin "16") (pinfunction "VCCB_16") (pintype "power_in"))
      (node (ref "U4") (pin "8") (pinfunction "VCC_8") (pintype "power_in"))
      (node (ref "U5") (pin "14") (pinfunction "VCC_14") (pintype "power_in"))
      (node (ref "U6") (pin "8") (pinfunction "VCC_8") (pintype "power_in"))
      (node (ref "U7") (pin "14") (pinfunction "VCC_14") (pintype "power_in"))
    )
    (net (code "39") (name "unconnected-(H1-Pad1)") (class "Default")
      (node (ref "H1") (pin "1") (pinfunction "1_1") (pintype "passive"))
    )
    (net (code "40") (name "unconnected-(H2-Pad1)") (class "Default")
      (node (ref "H2") (pin "1") (pinfunction "1_1") (pintype "passive"))
    )
    (net (code "41") (name "unconnected-(H3-Pad1)") (class "Default")
      (node (ref "H3") (pin "1") (pinfunction "1_1") (pintype "passive"))
    )
    (net (code "42") (name "unconnected-(H4-Pad1)") (class "Default")
      (node (ref "H4") (pin "1") (pinfunction "1_1") (pintype "passive"))
    )
    (net (code "43") (name "unconnected-(R14-Pad1)") (class "Default")
      (node (ref "R14") (pin "1") (pinfunction "1_1") (pintype "passive"))
    )
    (net (code "44") (name "unconnected-(U5-3A-Pad5)") (class "Default")
      (node (ref "U5") (pin "5") (pinfunction "3A_5") (pintype "input+no_connect"))
    )
    (net (code "45") (name "unconnected-(U5-3Y-Pad6)") (class "Default")
      (node (ref "U5") (pin "6") (pinfunction "3Y_6") (pintype "output+no_connect"))
    )
    (net (code "46") (name "unconnected-(U7-3A-Pad5)") (class "Default")
      (node (ref "U7") (pin "5") (pinfunction "3A_5") (pintype "input+no_connect"))
    )
    (net (code "47") (name "unconnected-(U7-3Y-Pad6)") (class "Default")
      (node (ref "U7") (pin "6") (pinfunction "3Y_6") (pintype "output+no_connect"))
    )
  )
)
